# LAm.net
KiCad netlist of a schematic drawn in EAGLE
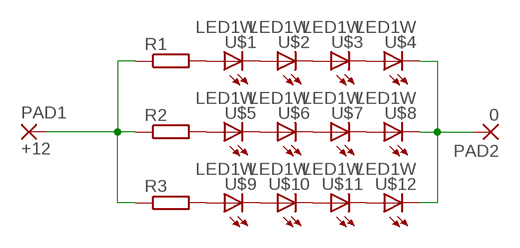
[diagram p0: schematic, sheet 1]

(export (version "E")
  (design (tool "Eeschema 10.0.6"))
  (components
    (comp (ref "PAD1")
      (value "+12")
      (footprint "eagle-import:SMD2,54-5,08")
      (libsource (lib "eagle-import") (part "SMD5"))
    )
    (comp (ref "PAD2")
      (value "0")
      (footprint "eagle-import:SMD2,54-5,08")
      (libsource (lib "eagle-import") (part "SMD5"))
    )
    (comp (ref "R1")
      (value "R-EU_R0805")
      (footprint "eagle-import:R0805")
      (libsource (lib "eagle-import") (part "R-EU_R0805"))
    )
    (comp (ref "R2")
      (value "R-EU_R0805")
      (footprint "eagle-import:R0805")
      (libsource (lib "eagle-import") (part "R-EU_R0805"))
    )
    (comp (ref "R3")
      (value "R-EU_R0805")
      (footprint "eagle-import:R0805")
      (libsource (lib "eagle-import") (part "R-EU_R0805"))
    )
    (comp (ref "U$1")
      (value "LED1W")
      (footprint "eagle-import:LED-1W")
      (libsource (lib "eagle-import") (part "LED1W"))
    )
    (comp (ref "U$2")
      (value "LED1W")
      (footprint "eagle-import:LED-1W")
      (libsource (lib "eagle-import") (part "LED1W"))
    )
    (comp (ref "U$3")
      (value "LED1W")
      (footprint "eagle-import:LED-1W")
      (libsource (lib "eagle-import") (part "LED1W"))
    )
    (comp (ref "U$4")
      (value "LED1W")
      (footprint "eagle-import:LED-1W")
      (libsource (lib "eagle-import") (part "LED1W"))
    )
    (comp (ref "U$5")
      (value "LED1W")
      (footprint "eagle-import:LED-1W")
      (libsource (lib "eagle-import") (part "LED1W"))
    )
    (comp (ref "U$6")
      (value "LED1W")
      (footprint "eagle-import:LED-1W")
      (libsource (lib "eagle-import") (part "LED1W"))
    )
    (comp (ref "U$7")
      (value "LED1W")
      (footprint "eagle-import:LED-1W")
      (libsource (lib "eagle-import") (part "LED1W"))
    )
    (comp (ref "U$8")
      (value "LED1W")
      (footprint "eagle-import:LED-1W")
      (libsource (lib "eagle-import") (part "LED1W"))
    )
    (comp (ref "U$9")
      (value "LED1W")
      (footprint "eagle-import:LED-1W")
      (libsource (lib "eagle-import") (part "LED1W"))
    )
    (comp (ref "U$10")
      (value "LED1W")
      (footprint "eagle-import:LED-1W")
      (libsource (lib "eagle-import") (part "LED1W"))
    )
    (comp (ref "U$11")
      (value "LED1W")
      (footprint "eagle-import:LED-1W")
      (libsource (lib "eagle-import") (part "LED1W"))
    )
    (comp (ref "U$12")
      (value "LED1W")
      (footprint "eagle-import:LED-1W")
      (libsource (lib "eagle-import") (part "LED1W"))
    )
  )
  (nets
    (net (code "1") (name "Net-(PAD1-P)") (class "Default")
      (node (ref "PAD1") (pin "1") (pinfunction "P_1") (pintype "passive"))
      (node (ref "R1") (pin "1") (pinfunction "1_1") (pintype "passive"))
      (node (ref "R2") (pin "1") (pinfunction "1_1") (pintype "passive"))
      (node (ref "R3") (pin "1") (pinfunction "1_1") (pintype "passive"))
    )
    (net (code "2") (name "Net-(PAD2-P)") (class "Default")
      (node (ref "PAD2") (pin "1") (pinfunction "P_1") (pintype "passive"))
      (node (ref "U$12") (pin "K") (pinfunction "C_K") (pintype "passive"))
      (node (ref "U$4") (pin "K") (pinfunction "C_K") (pintype "passive"))
      (node (ref "U$8") (pin "K") (pinfunction "C_K") (pintype "passive"))
    )
    (net (code "3") (name "Net-(R1-Pad2)") (class "Default")
      (node (ref "R1") (pin "2") (pinfunction "2_2") (pintype "passive"))
      (node (ref "U$1") (pin "A") (pinfunction "A_A") (pintype "passive"))
    )
    (net (code "4") (name "Net-(R2-Pad2)") (class "Default")
      (node (ref "R2") (pin "2") (pinfunction "2_2") (pintype "passive"))
      (node (ref "U$5") (pin "A") (pinfunction "A_A") (pintype "passive"))
    )
    (net (code "5") (name "Net-(R3-Pad2)") (class "Default")
      (node (ref "R3") (pin "2") (pinfunction "2_2") (pintype "passive"))
      (node (ref "U$9") (pin "A") (pinfunction "A_A") (pintype "passive"))
    )
    (net (code "6") (name "Net-(U$1-C)") (class "Default")
      (node (ref "U$1") (pin "K") (pinfunction "C_K") (pintype "passive"))
      (node (ref "U$2") (pin "A") (pinfunction "A_A") (pintype "passive"))
    )
    (net (code "7") (name "Net-(U$2-C)") (class "Default")
      (node (ref "U$2") (pin "K") (pinfunction "C_K") (pintype "passive"))
      (node (ref "U$3") (pin "A") (pinfunction "A_A") (pintype "passive"))
    )
    (net (code "8") (name "Net-(U$3-C)") (class "Default")
      (node (ref "U$3") (pin "K") (pinfunction "C_K") (pintype "passive"))
      (node (ref "U$4") (pin "A") (pinfunction "A_A") (pintype "passive"))
    )
    (net (code "9") (name "Net-(U$5-C)") (class "Default")
      (node (ref "U$5") (pin "K") (pinfunction "C_K") (pintype "passive"))
      (node (ref "U$6") (pin "A") (pinfunction "A_A") (pintype "passive"))
    )
    (net (code "10") (name "Net-(U$6-C)") (class "Default")
      (node (ref "U$6") (pin "K") (pinfunction "C_K") (pintype "passive"))
      (node (ref "U$7") (pin "A") (pinfunction "A_A") (pintype "passive"))
    )
    (net (code "11") (name "Net-(U$7-C)") (class "Default")
      (node (ref "U$7") (pin "K") (pinfunction "C_K") (pintype "passive"))
      (node (ref "U$8") (pin "A") (pinfunction "A_A") (pintype "passive"))
    )
    (net (code "12") (name "Net-(U$9-C)") (class "Default")
      (node (ref "U$10") (pin "A") (pinfunction "A_A") (pintype "passive"))
      (node (ref "U$9") (pin "K") (pinfunction "C_K") (pintype "passive"))
    )
    (net (code "13") (name "Net-(U$10-C)") (class "Default")
      (node (ref "U$10") (pin "K") (pinfunction "C_K") (pintype "passive"))
      (node (ref "U$11") (pin "A") (pinfunction "A_A") (pintype "passive"))
    )
    (net (code "14") (name "Net-(U$11-C)") (class "Default")
      (node (ref "U$11") (pin "K") (pinfunction "C_K") (pintype "passive"))
      (node (ref "U$12") (pin "A") (pinfunction "A_A") (pintype "passive"))
    )
  )
)
